# Sheet3.net
KiCad netlist of a schematic drawn in Altium Designer
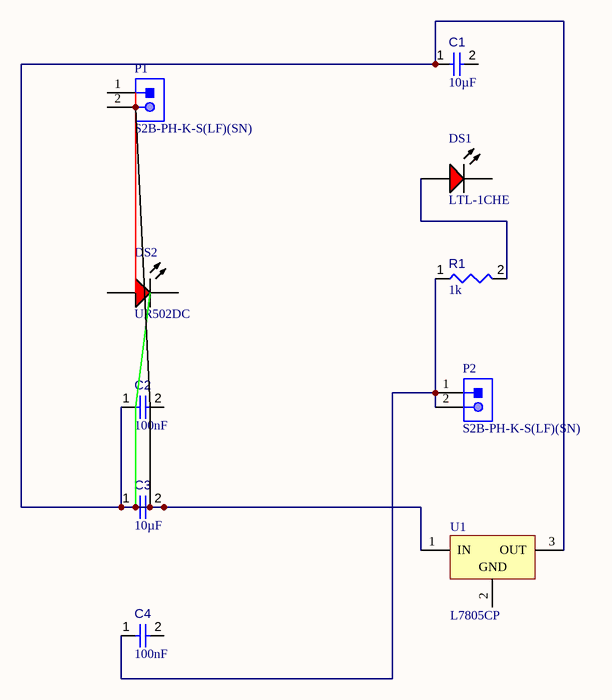
[diagram p0: Sheet3.SchDoc]

(export (version "E")
  (design (tool "Eeschema 10.0.6"))
  (components
    (comp (ref "C1")
      (value "10µF")
      (footprint "CAPC0805(2012)145_L")
      (description "Chip Capacitor, 10µF +/-20%, 25V, 0805, Thickness 1.45 mm")
      (fields (field (name "TOLERANCE") "10%") (field (name "Comment") "Capacitor 10µF +/-20% 25V 0805"))
      (libsource (lib "EFRAIN ALVARADO") (part "CAP-NP-2"))
    )
    (comp (ref "C2")
      (value "100nF")
      (footprint "CAPC1005X56X25LL10T15")
      (description "Chip Capacitor, 0.1 uF, +/- 5%, 16 V, 0402 (1005 Metric)")
      (fields (field (name "TOLERANCE") "5%") (field (name "Comment") "Capacitor 0.1 uF +/- 5% 16 V 0402"))
      (libsource (lib "EFRAIN ALVARADO") (part "CAP-NP-2"))
    )
    (comp (ref "C3")
      (value "10µF")
      (footprint "CAPC0805(2012)145_L")
      (description "Chip Capacitor, 10µF +/-20%, 25V, 0805, Thickness 1.45 mm")
      (fields (field (name "TOLERANCE") "10%") (field (name "Comment") "Capacitor 10µF +/-20% 25V 0805"))
      (libsource (lib "EFRAIN ALVARADO") (part "CAP-NP-2"))
    )
    (comp (ref "C4")
      (value "100nF")
      (footprint "CAPC0402(1005)60_L")
      (description "Chip Capacitor, 100nF +/-20%, 25V, 0402, Thickness 0.6 mm")
      (fields (field (name "TOLERANCE") "10%") (field (name "Comment") "Capacitor 100nF +/-20% 25V 0402"))
      (libsource (lib "EFRAIN ALVARADO") (part "CAP-NP-2"))
    )
    (comp (ref "DS1")
      (value "LTL-1CHE")
      (footprint "INDPR60-254-520X380X650")
      (description "LED Uni-Color Red, 100 mW, 30 mA, -55 to 100 degC, 2-Pin THD, RoHS, Bulk")
      (fields (field (name "MANUFACTURER") "Lite-On"))
      (libsource (lib "EFRAIN ALVARADO") (part "LED-RED-AK-2"))
    )
    (comp (ref "DS2")
      (value "UR502DC")
      (footprint "CGX-UR502DC")
      (description "Red LED, 80 mW, 30 mA, -25 to 85 degC, 2-Pin THD")
      (fields (field (name "POWER") "80mW") (field (name "MANUFACTURER") "Shenzhen CGX"))
      (libsource (lib "EFRAIN ALVARADO") (part "LED-RED-AK-2"))
    )
    (comp (ref "P1")
      (value "S2B-PH-K-S(LF)(SN)")
      (footprint "JST-S2B-PH-K-S_V")
      (fields (field (name "MANUFACTURER") "Japan Solderless Terminals"))
      (libsource (lib "EFRAIN ALVARADO") (part "CN-1P-M-R2"))
    )
    (comp (ref "P2")
      (value "S2B-PH-K-S(LF)(SN)")
      (footprint "JST-S2B-PH-K-S_V")
      (fields (field (name "MANUFACTURER") "Japan Solderless Terminals"))
      (libsource (lib "EFRAIN ALVARADO") (part "CN-1P-M-R2"))
    )
    (comp (ref "R1")
      (value "1k")
      (footprint "RESC0402(1005)_L")
      (description "1K 0.063W 5% 0402 (1005 Metric)  SMD")
      (fields (field (name "POWER") "63mW") (field (name "TOLERANCE") "5%"))
      (libsource (lib "EFRAIN ALVARADO") (part "1KR2J"))
    )
    (comp (ref "U1")
      (value "L7805CP")
      (footprint "TO220FP")
      (description "Positive Voltage Regulator, 5V, 3-Pin TO-220FP")
      (libsource (lib "Altium Content Vault") (part "PM-REG-L4940-SIL3"))
    )
  )
  (nets
    (net (code "1") (name "Net-(C4-Pad1)") (class "Default")
      (node (ref "C4") (pin "1") (pinfunction "1_1") (pintype "passive"))
      (node (ref "P2") (pin "1") (pinfunction "1_1") (pintype "passive"))
      (node (ref "P2") (pin "2") (pinfunction "2_2") (pintype "passive"))
      (node (ref "R1") (pin "1") (pinfunction "1_1") (pintype "passive"))
    )
    (net (code "2") (name "Net-(DS1-A)") (class "Default")
      (node (ref "DS1") (pin "1") (pinfunction "A_1") (pintype "passive"))
      (node (ref "R1") (pin "2") (pinfunction "2_2") (pintype "passive"))
    )
    (net (code "3") (name "Net-(U1-IN)") (class "Default")
      (node (ref "C1") (pin "1") (pinfunction "1_1") (pintype "passive"))
      (node (ref "C2") (pin "1") (pinfunction "1_1") (pintype "passive"))
      (node (ref "C3") (pin "1") (pinfunction "1_1") (pintype "passive"))
      (node (ref "C3") (pin "2") (pinfunction "2_2") (pintype "passive"))
      (node (ref "U1") (pin "1") (pinfunction "IN_1") (pintype "power_in"))
      (node (ref "U1") (pin "3") (pinfunction "OUT_3") (pintype "power_in"))
    )
    (net (code "4") (name "unconnected-(C1-Pad2)") (class "Default")
      (node (ref "C1") (pin "2") (pinfunction "2_2") (pintype "passive"))
    )
    (net (code "5") (name "unconnected-(C2-Pad2)") (class "Default")
      (node (ref "C2") (pin "2") (pinfunction "2_2") (pintype "passive"))
    )
    (net (code "6") (name "unconnected-(C4-Pad2)") (class "Default")
      (node (ref "C4") (pin "2") (pinfunction "2_2") (pintype "passive"))
    )
    (net (code "7") (name "unconnected-(DS1-K-Pad2)") (class "Default")
      (node (ref "DS1") (pin "2") (pinfunction "K_2") (pintype "passive"))
    )
    (net (code "8") (name "unconnected-(DS2-A-Pad1)") (class "Default")
      (node (ref "DS2") (pin "1") (pinfunction "A_1") (pintype "passive"))
    )
    (net (code "9") (name "unconnected-(DS2-K-Pad2)") (class "Default")
      (node (ref "DS2") (pin "2") (pinfunction "K_2") (pintype "passive"))
    )
    (net (code "10") (name "unconnected-(P1-Pad1)") (class "Default")
      (node (ref "P1") (pin "1") (pinfunction "1_1") (pintype "passive"))
    )
    (net (code "11") (name "unconnected-(P1-Pad2)") (class "Default")
      (node (ref "P1") (pin "2") (pinfunction "2_2") (pintype "passive"))
    )
    (net (code "12") (name "unconnected-(U1-GND-Pad2)") (class "Default")
      (node (ref "U1") (pin "2") (pinfunction "GND_2") (pintype "power_in"))
    )
  )
)
